# AIRZAI_LID_BD_REVB_Sheet1.net
KiCad netlist of a schematic drawn in Altium Designer
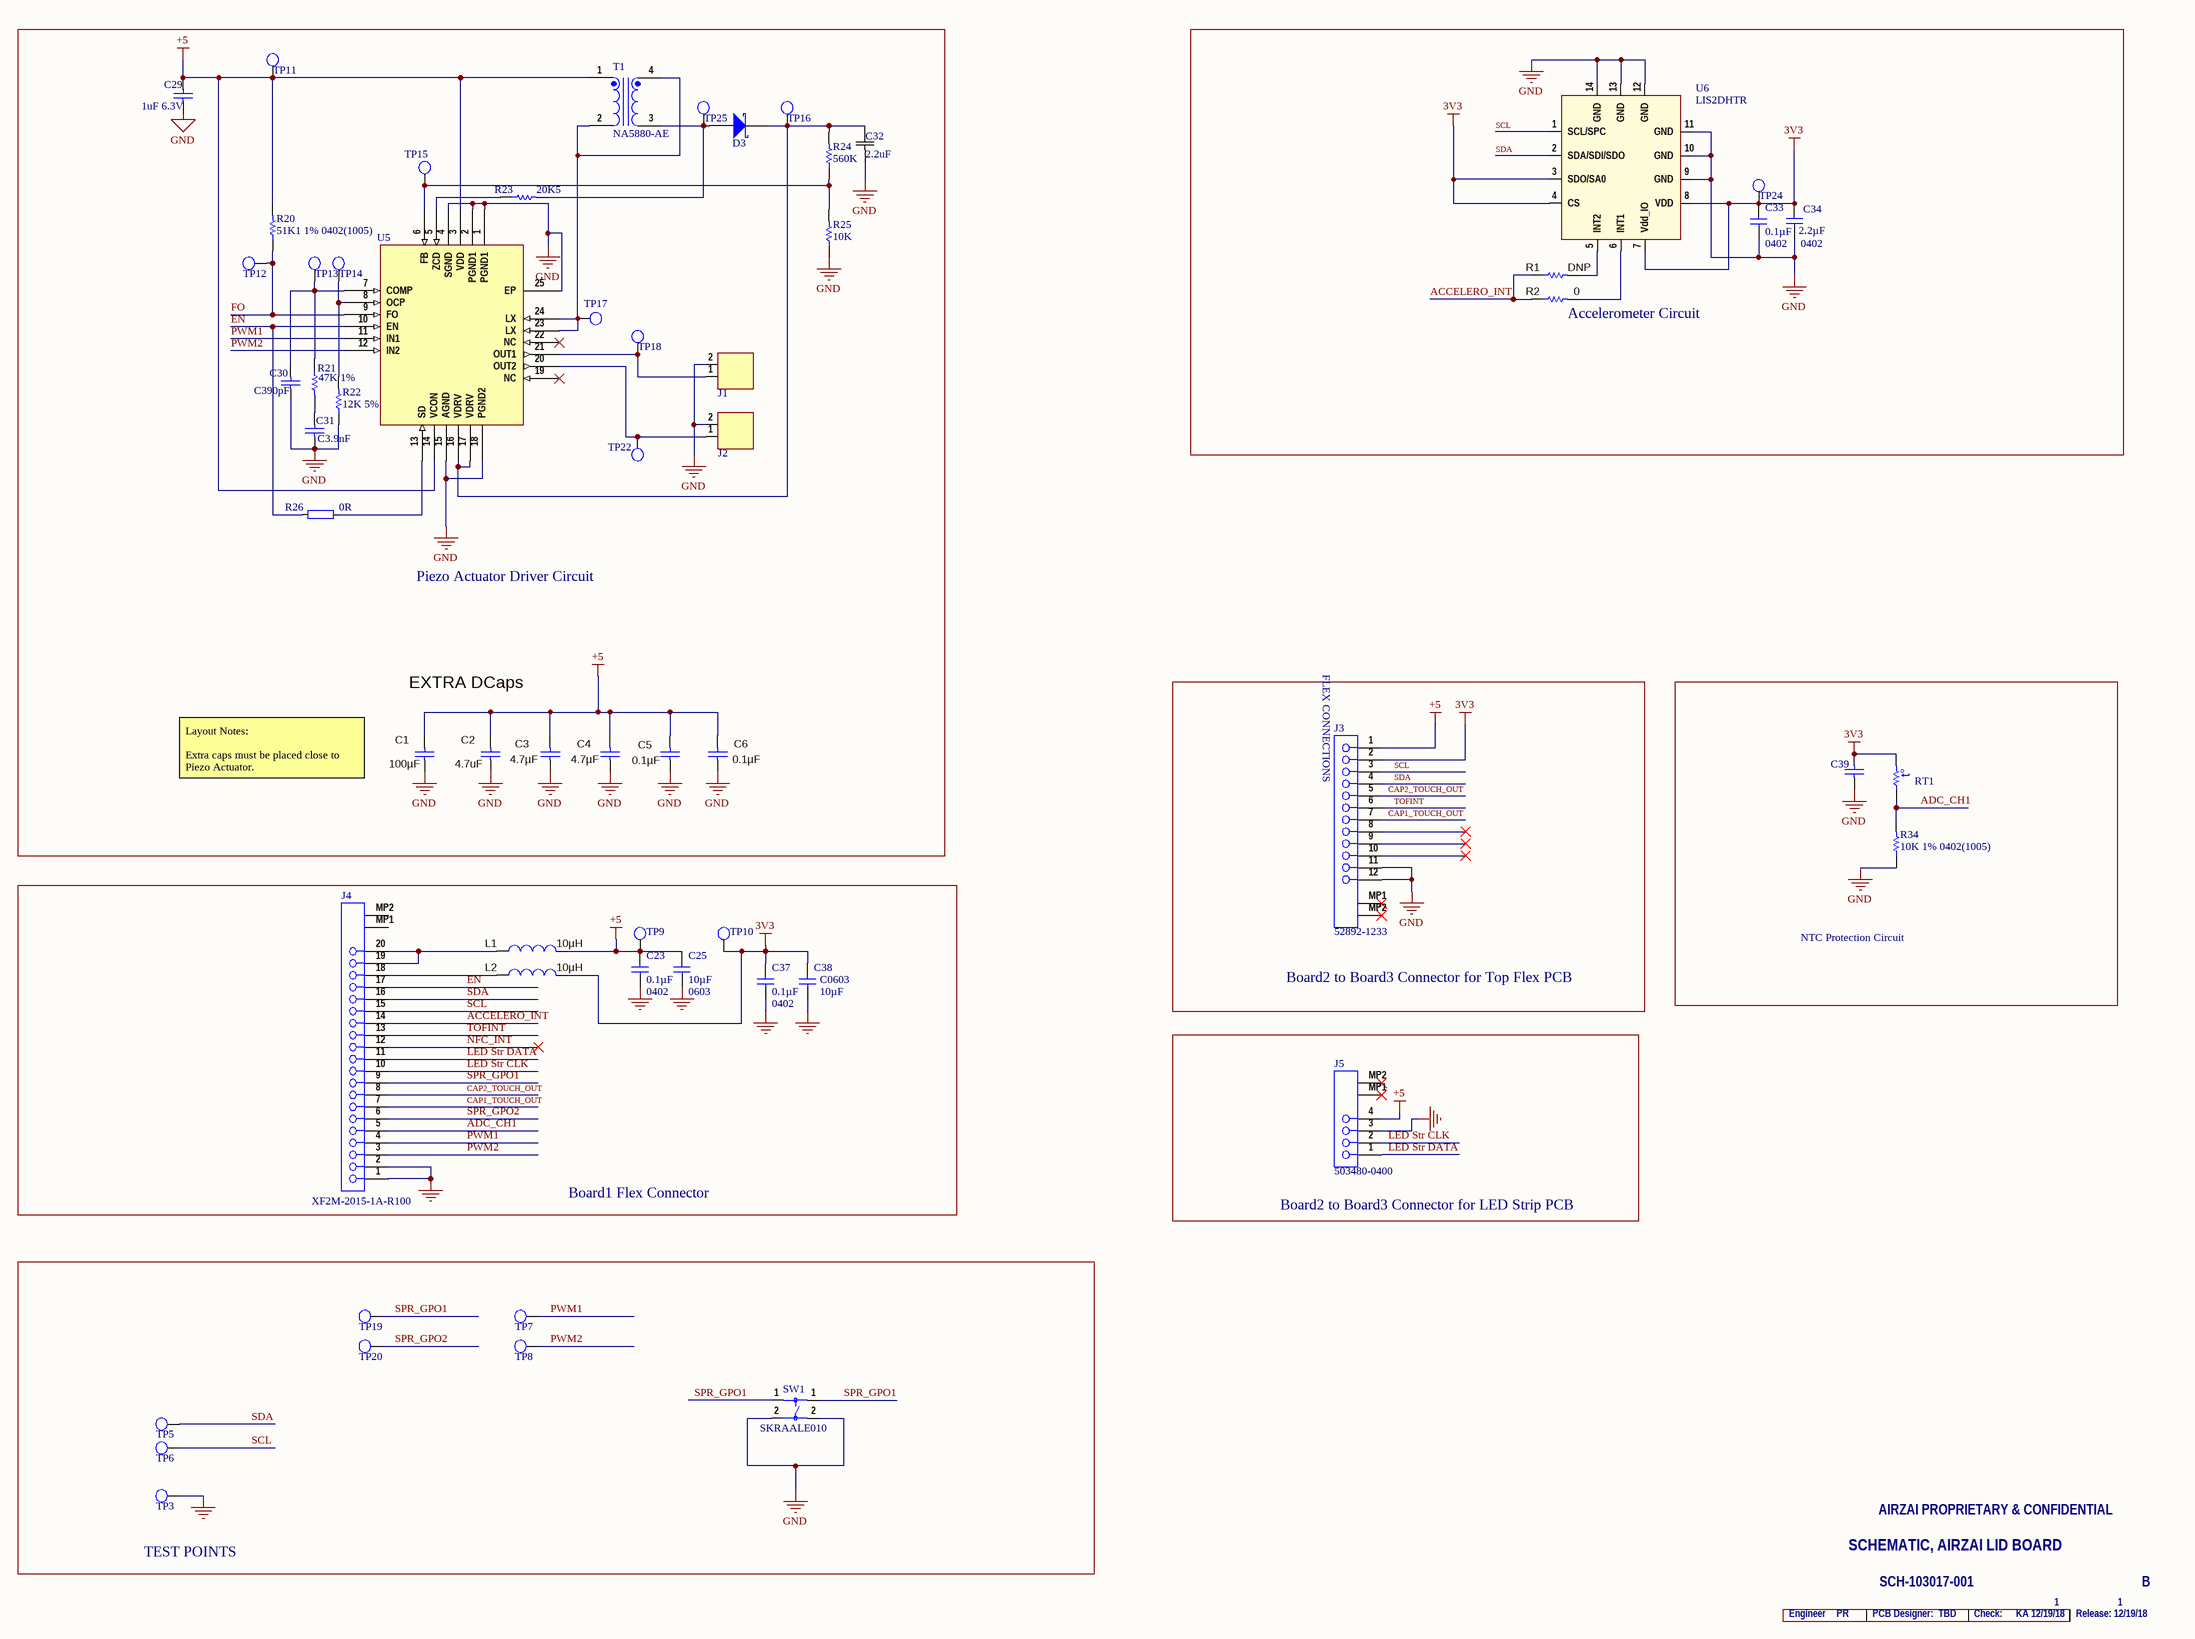
[diagram p0: AIRZAI_LID_BD_REVB Sheet1.SchDoc]

(export (version "E")
  (design (tool "Eeschema 10.0.6"))
  (components
    (comp (ref "C1")
      (value "GRM31CR60J107ME39L")
      (footprint "1206_180")
      (description "CAP, CERM, 100 µF, 6.3 V, +/- 20%, X5R, 1206")
      (fields
        (field (name "VALUEDISPLAYED") "100µF")
        (field (name "MANUFACTURER") "MuRata")
        (field (name "PUBLISHER") "Texas Instruments")
      )
      (libsource (lib "Capacitor_Ceramic") (part "GRM31CR60J107ME39L"))
    )
    (comp (ref "C2")
      (value "4.7uF")
      (footprint "SM0402_BTD.1SM_ACT_H55_CAP_WSS")
      (description "CAP, CERM, 4.7 µF, 6.3 V, +/- 20%, X5R, 0402")
      (fields (field (name "PARTNUMBER") "C1005X5R0J475M050BC") (field (name "MANUFACTURER") "TDK"))
      (libsource (lib "Capacitor_Ceramic") (part "C1005X5R0J475M050BC"))
    )
    (comp (ref "C3")
      (value "C1005X5R0J475M050BC")
      (footprint "SM0402_BTD.1SM_ACT_H55_CAP_WSS")
      (description "CAP, CERM, 4.7 µF, 6.3 V, +/- 20%, X5R, 0402")
      (fields
        (field (name "VALUEDISPLAYED") "4.7µF")
        (field (name "MANUFACTURER") "TDK")
        (field (name "PUBLISHER") "Texas Instruments")
      )
      (libsource (lib "Capacitor_Ceramic") (part "C1005X5R0J475M050BC"))
    )
    (comp (ref "C4")
      (value "C1005X5R0J475M050BC")
      (footprint "SM0402_BTD.1SM_ACT_H55_CAP_WSS")
      (description "CAP, CERM, 4.7 µF, 6.3 V, +/- 20%, X5R, 0402")
      (fields
        (field (name "VALUEDISPLAYED") "4.7µF")
        (field (name "MANUFACTURER") "TDK")
        (field (name "PUBLISHER") "Texas Instruments")
      )
      (libsource (lib "Capacitor_Ceramic") (part "C1005X5R0J475M050BC"))
    )
    (comp (ref "C5")
      (value "C1005X5R1A104K050BA")
      (footprint "SM0402_BTD.1SM_ACT_H55_CAP_WSS")
      (description "CAP, CERM, 0.1 µF, 10 V, +/- 10%, X5R, 0402")
      (fields
        (field (name "VALUEDISPLAYED") "0.1µF")
        (field (name "MANUFACTURER") "TDK")
        (field (name "PUBLISHER") "Texas Instruments")
      )
      (libsource (lib "Capacitor_Ceramic") (part "C1005X5R1A104K050BA"))
    )
    (comp (ref "C6")
      (value "C1005X5R1A104K050BA")
      (footprint "SM0402_BTD.1SM_ACT_H55_CAP_WSS")
      (description "CAP, CERM, 0.1 µF, 10 V, +/- 10%, X5R, 0402")
      (fields
        (field (name "VALUEDISPLAYED") "0.1µF")
        (field (name "MANUFACTURER") "TDK")
        (field (name "PUBLISHER") "Texas Instruments")
      )
      (libsource (lib "Capacitor_Ceramic") (part "C1005X5R1A104K050BA"))
    )
    (comp (ref "C23")
      (value "0.1µF")
      (footprint "0402")
      (description "Capacitor, X7R, ±10%")
      (fields (field (name "MANUFACTURER") "TDK") (field (name "MANUFACTURER PART NUMBER") "C1005X7R1C104K"))
      (libsource (lib "Nordic Passive DB") (part "CAP"))
    )
    (comp (ref "C25")
      (value "10µF")
      (footprint "0603")
      (description "6.3volts X5R 20%")
      (fields
        (field (name "MANUFACTURER") "MURATA")
        (field (name "MANUFACTURER PART NUMBER") "GRM188R60J106ME47D")
      )
      (libsource (lib "Nordic Passive DB") (part "CAP"))
    )
    (comp (ref "C29")
      (value "1uF 6.3V")
      (footprint "CAPC0402(1005)60_M")
      (description "CAP 1uF 6.3V ±10% 0402 (1005 Metric) Thickness 0.6mm SMD")
      (fields (field (name "TOLERANCE") "Â±10%") (field (name "MANUFACTURER") "MURATA"))
      (libsource (lib "") (part "CAP_1"))
    )
    (comp (ref "C30")
      (value "C390pF")
      (footprint "CAPC0402(1005)60_M")
      (description "CAP 390pF 50V ±20% 0402 (1005 Metric) Thickness 0.6mm SMD")
      (fields (field (name "TOLERANCE") "Â±20%") (field (name "MANUFACTURER") "KEMET"))
      (libsource (lib "AIRZAI_LID_BD_REVA") (part "CAP"))
    )
    (comp (ref "C31")
      (value "C3.9nF")
      (footprint "CAPC0402(1005)60_M")
      (description "CAP 3.9nF 50V ±10% 0402 (1005 Metric) Thickness 0.6mm SMD")
      (fields (field (name "TOLERANCE") "Â±10%") (field (name "MANUFACTURER") "TDK"))
      (libsource (lib "") (part "CAP_1"))
    )
    (comp (ref "C32")
      (value "2.2uF")
      (footprint "C1210_N")
      (description "Imported")
      (fields
        (field (name "MANUFACTURER_PART_NUMBER") "C3225JB2A225K230AB")
        (field (name "MANUFACTURER") "TDK")
      )
      (libsource (lib "C3225JB2A225K230AB") (part "C3225JB2A225K230"))
    )
    (comp (ref "C33")
      (value "0.1µF")
      (footprint "0402")
      (description "Capacitor, X7R, ±10%")
      (fields (field (name "MANUFACTURER") "TDK") (field (name "MANUFACTURER PART NUMBER") "C1005X7R1C104K"))
      (libsource (lib "Nordic Passive DB") (part "CAP"))
    )
    (comp (ref "C34")
      (value "2.2µF")
      (footprint "0402")
      (description "Capacitor, X7R, ±10%")
      (fields (field (name "MANUFACTURER") "TDK") (field (name "MANUFACTURER PART NUMBER") "C1005X5R0J225M"))
      (libsource (lib "Nordic Passive DB") (part "CAP"))
    )
    (comp (ref "C37")
      (value "0.1µF")
      (footprint "0402")
      (description "Capacitor, X7R, ±10%")
      (fields (field (name "MANUFACTURER") "TDK") (field (name "MANUFACTURER PART NUMBER") "C1005X7R1C104K"))
      (libsource (lib "Nordic Passive DB") (part "CAP"))
    )
    (comp (ref "C38")
      (value "10µF")
      (footprint "C0603")
      (description "Capacitor, X7R, ±10%")
      (fields
        (field (name "MANUFACTURER") "MURATA")
        (field (name "MANUFACTURER PART NUMBER") "GRM188R60J106ME47D")
      )
      (libsource (lib "Nordic Passive DB") (part "CAP"))
    )
    (comp (ref "C39")
      (value "CAP 100nF 10V 0402(1005)")
      (footprint "CAPC0402(1005)60_M")
      (description "CAP 100nF 10V ±10% 0402 (1005 Metric) Thickness 0.6mm SMD")
      (fields (field (name "TOLERANCE") "Â±10%") (field (name "MANUFACTURER") "Yageo"))
      (libsource (lib "") (part "CAP_1"))
    )
    (comp (ref "D3")
      (value "STPS2H100A")
      (footprint "STM-SMA-2_V")
      (description "Power Schottky Rectifier, 2 A, 100 V, 2-Pin SMD (SMA), RoHS, Tape and Reel")
      (fields (field (name "MANUFACTURER") "STMicroelectronics"))
      (libsource (lib "AIRZAI_LID_BD_REVA") (part "DSKY-AK-2"))
    )
    (comp (ref "J1")
      (value "~")
      (footprint "CON_78171_0002")
      (fields (field (name "MANUFACTURER PART NUMBER") "781710002") (field (name "MANUFACTURER") "MOLEX"))
      (libsource (lib "DFM_JBKEGSVS_Library") (part "CONN_BM02B_SURS_TF"))
    )
    (comp (ref "J2")
      (value "~")
      (footprint "CON_78171_0002")
      (fields (field (name "MANUFACTURER PART NUMBER") "781710002") (field (name "MANUFACTURER") "MOLEX"))
      (libsource (lib "DFM_JBKEGSVS_Library") (part "CONN_BM02B_SURS_TF"))
    )
    (comp (ref "J3")
      (value "52892-1233")
      (footprint "MOLX-52892-1233")
      (fields (field (name "MANUFACTURER") "MOLEX") (field (name "MANUFACTURER PART NUMBER") "0528921233"))
      (libsource (lib "AIRZAI_LID_BD_REVA") (part "MOLX-52892-1233"))
    )
    (comp (ref "J4")
      (value "XF2M-2015-1A-R100")
      (footprint "Omron_XF2M-2015-1A_0")
      (fields (field (name "MANUFACTURER") "OMRON ELECTRONIC COMPONENTS"))
      (libsource (lib "AIRZAI_LID_BD_REVA") (part "XF2M-2015-1A-R100"))
    )
    (comp (ref "J5")
      (value "503480-0400")
      (footprint "MOLX-503480-0400")
      (fields (field (name "MANUFACTURER") "Molex"))
      (libsource (lib "AIRZAI_LID_BD_REVA") (part "503480-0400"))
    )
    (comp (ref "L1")
      (value "CB2012T100KR")
      (footprint "0805")
      (description "Inductor, 10 µH, 0.5A, 0.65 ohm, SMD")
      (fields
        (field (name "MANUFACTURER") "Taiyo Yuden")
        (field (name "TOLERANCE") "10%")
        (field (name "VALUEDISPLAYED") "10µH")
      )
      (libsource (lib "AIRZAI_LED_SENSE_FLEX_REVA") (part "CB2012T100KR"))
    )
    (comp (ref "L2")
      (value "CB2012T100KR")
      (footprint "0805")
      (description "Inductor, 10 µH, 0.5A, 0.65 ohm, SMD")
      (fields
        (field (name "MANUFACTURER") "Taiyo Yuden")
        (field (name "TOLERANCE") "10%")
        (field (name "VALUEDISPLAYED") "10µH")
      )
      (libsource (lib "AIRZAI_LED_SENSE_FLEX_REVA") (part "CB2012T100KR"))
    )
    (comp (ref "R1")
      (value "DNP")
      (footprint "0402")
      (description "RES, DNP, 0402")
      (libsource (lib "Resistor_0402") (part "ERJ-2GE0R00X"))
    )
    (comp (ref "R2")
      (value "ERJ-2GE0R00X")
      (footprint "0402")
      (description "RES, 0, 5%, 0.063 W, 0402")
      (fields
        (field (name "VALUEDISPLAYED") "0")
        (field (name "MANUFACTURER") "Panasonic")
        (field (name "PUBLISHER") "Texas Instruments")
      )
      (libsource (lib "Resistor_0402") (part "ERJ-2GE0R00X"))
    )
    (comp (ref "R20")
      (value "51K1 1% 0402(1005)")
      (footprint "0402")
      (description "51K1 0.063W 1% 0402 (1005 Metric)  SMD")
      (fields (field (name "POWER") "0.063 W") (field (name "TOLERANCE") "1 %"))
      (libsource (lib "AIRZAI_LID_BD_REVA") (part "RES"))
    )
    (comp (ref "R21")
      (value "47K 1%")
      (footprint "0402")
      (description "47K 0.063W 1% 0402 (1005 Metric)  SMD")
      (fields (field (name "POWER") "0.063 W") (field (name "TOLERANCE") "1 %"))
      (libsource (lib "") (part "RES_2"))
    )
    (comp (ref "R22")
      (value "12K 5%")
      (footprint "0402")
      (description "12K 0.063W 5% 0402 (1005 Metric)  SMD")
      (fields (field (name "TOLERANCE") "5 %") (field (name "POWER") "0.063 W"))
      (libsource (lib "AIRZAI_LID_BD_REVA") (part "RES"))
    )
    (comp (ref "R23")
      (value "20K5")
      (footprint "0402")
      (description "20K5 0.063W 1% 0402 (1005 Metric)  SMD")
      (fields (field (name "POWER") "0.063 W") (field (name "TOLERANCE") "1 %"))
      (libsource (lib "") (part "RES_1"))
    )
    (comp (ref "R24")
      (value "560K")
      (footprint "0402")
      (description "560K 0.063W 1% 0402 (1005 Metric)  SMD")
      (fields (field (name "POWER") "0.063 W") (field (name "TOLERANCE") "1 %"))
      (libsource (lib "AIRZAI_LID_BD_REVA") (part "RES"))
    )
    (comp (ref "R25")
      (value "10K")
      (footprint "0402")
      (description "10K 0.063W 5% 0402 (1005 Metric)  SMD")
      (fields (field (name "TOLERANCE") "5 %") (field (name "POWER") "0.063 W"))
      (libsource (lib "AIRZAI_LID_BD_REVA") (part "RES"))
    )
    (comp (ref "R26")
      (value "0R")
      (footprint "0402")
      (description "Resistor, ±1%, 0.063W")
      (fields
        (field (name "MANUFACTURER") "Panasonic")
        (field (name "MANUFACTURER PART NUMBER") "ERJ-2GE0R00X")
      )
      (libsource (lib "Nordic Passive DB") (part "RES_1"))
    )
    (comp (ref "R34")
      (value "10K 1% 0402(1005)")
      (footprint "0402")
      (description "10K 0.063W 1% 0402 (1005 Metric)  SMD")
      (fields (field (name "TOLERANCE") "1 %") (field (name "POWER") "0.063 W"))
      (libsource (lib "AIRZAI_LID_BD_REVA") (part "RES"))
    )
    (comp (ref "RT1")
      (value "NCP18XH103F03RB")
      (footprint "MURA-NCP18XH103F03RB-2_V")
      (description "NTC Thermistor, 10 KOhm, +/- 1%, 0.1 W, -40 to 125 degC, 0603 (1608 Metric), RoHS, Tape and Reel")
      (fields (field (name "MANUFACTURER") "Murata") (field (name "TOLERANCE") "1 %"))
      (libsource (lib "AIRZAI_LID_BD_REVA") (part "MURA-NCP18XH103F03RB-2"))
    )
    (comp (ref "SW1")
      (value "SKRAALE010")
      (footprint "SW_ALPS_SKRAALE010")
      (fields (field (name "MANUFACTURER") "ALPS") (field (name "MANUFACTURER PART NUMBER") "SKRAAKE010"))
      (libsource (lib "DFM_JBKEGSVS_Library") (part "SW_SKRAALE010"))
    )
    (comp (ref "T1")
      (value "NA5880-AE")
      (footprint "Coilcraft_NA5880-AE_MFG")
      (fields (field (name "MANUFACTURER") "CoilCraft") (field (name "TOLERANCE") "20%"))
      (libsource (lib "AIRZAI_LID_BD_REVA") (part "TRANS-DOT-1-1-4"))
    )
    (comp (ref "TP3")
      (value "TESTPOINT")
      (footprint "TP_0.9MM")
      (libsource (lib "DFM_JBKEGSVS_Library") (part "TESTPOINT"))
    )
    (comp (ref "TP5")
      (value "TESTPOINT")
      (footprint "TP_0.9MM")
      (libsource (lib "DFM_JBKEGSVS_Library") (part "TESTPOINT"))
    )
    (comp (ref "TP6")
      (value "TESTPOINT")
      (footprint "TP_0.9MM")
      (libsource (lib "DFM_JBKEGSVS_Library") (part "TESTPOINT"))
    )
    (comp (ref "TP7")
      (value "TESTPOINT")
      (footprint "TP_0.9MM")
      (libsource (lib "DFM_JBKEGSVS_Library") (part "TESTPOINT"))
    )
    (comp (ref "TP8")
      (value "TESTPOINT")
      (footprint "TP_0.9MM")
      (libsource (lib "DFM_JBKEGSVS_Library") (part "TESTPOINT"))
    )
    (comp (ref "TP9")
      (value "TESTPOINT")
      (footprint "TP_0.9MM")
      (libsource (lib "DFM_JBKEGSVS_Library") (part "TESTPOINT"))
    )
    (comp (ref "TP10")
      (value "TESTPOINT")
      (footprint "TP_0.9MM")
      (libsource (lib "DFM_JBKEGSVS_Library") (part "TESTPOINT"))
    )
    (comp (ref "TP11")
      (value "TESTPOINT")
      (footprint "TP_0.9MM")
      (libsource (lib "AIRZAI_LID_BD_REVA") (part "TESTPOINT"))
    )
    (comp (ref "TP12")
      (value "TESTPOINT")
      (footprint "TP_0.9MM")
      (libsource (lib "AIRZAI_LID_BD_REVA") (part "TESTPOINT"))
    )
    (comp (ref "TP13")
      (value "TESTPOINT")
      (footprint "TP_0.9MM")
      (libsource (lib "AIRZAI_LID_BD_REVA") (part "TESTPOINT"))
    )
    (comp (ref "TP14")
      (value "TESTPOINT")
      (footprint "TP_0.9MM")
      (libsource (lib "AIRZAI_LID_BD_REVA") (part "TESTPOINT"))
    )
    (comp (ref "TP15")
      (value "TESTPOINT")
      (footprint "TP_0.9MM")
      (libsource (lib "AIRZAI_LID_BD_REVA") (part "TESTPOINT"))
    )
    (comp (ref "TP16")
      (value "TESTPOINT")
      (footprint "TP_0.9MM")
      (libsource (lib "AIRZAI_LID_BD_REVA") (part "TESTPOINT"))
    )
    (comp (ref "TP17")
      (value "TESTPOINT")
      (footprint "TP_0.9MM")
      (libsource (lib "AIRZAI_LID_BD_REVA") (part "TESTPOINT"))
    )
    (comp (ref "TP18")
      (value "TESTPOINT")
      (footprint "TP_0.9MM")
      (libsource (lib "AIRZAI_LID_BD_REVA") (part "TESTPOINT"))
    )
    (comp (ref "TP19")
      (value "TESTPOINT")
      (footprint "TP_0.9MM")
      (libsource (lib "DFM_JBKEGSVS_Library") (part "TESTPOINT"))
    )
    (comp (ref "TP20")
      (value "TESTPOINT")
      (footprint "TP_0.9MM")
      (libsource (lib "DFM_JBKEGSVS_Library") (part "TESTPOINT"))
    )
    (comp (ref "TP22")
      (value "TESTPOINT")
      (footprint "TP_0.9MM")
      (libsource (lib "AIRZAI_LID_BD_REVA") (part "TESTPOINT"))
    )
    (comp (ref "TP24")
      (value "TESTPOINT")
      (footprint "TP_0.9MM")
      (libsource (lib "AIRZAI_LID_BD_REVA") (part "TESTPOINT"))
    )
    (comp (ref "TP25")
      (value "TESTPOINT")
      (footprint "TP_0.9MM")
      (libsource (lib "AIRZAI_LID_BD_REVA") (part "TESTPOINT"))
    )
    (comp (ref "U5")
      (value "FAN8841MPXCT-ND")
      (footprint "WFQFN-24-FAN8841MPX")
      (description "IC PIEZO ACTUATOR DVR 24MLP")
      (fields
        (field (name "MANUFACTURER") "ON Semiconductor")
        (field (name "MANUFACTURER PART NUMBER") "FAN8841MPX")
      )
      (libsource (lib "AIRZAI_LID_BD_REVA") (part "FAN8841MPXCT-ND"))
    )
    (comp (ref "U6")
      (value "LIS2DHTR")
      (footprint "STM-LGA-14_L")
      (fields (field (name "MANUFACTURER") "ST"))
      (libsource (lib "AIRZAI_LID_BD_REVA") (part "LIS2DH"))
    )
  )
  (nets
    (net (code "1") (name "+5") (class "Default")
      (node (ref "C1") (pin "1") (pinfunction "1_1") (pintype "passive"))
      (node (ref "C2") (pin "1") (pinfunction "1_1") (pintype "passive"))
      (node (ref "C23") (pin "1") (pinfunction "1_1") (pintype "passive"))
      (node (ref "C25") (pin "1") (pinfunction "1_1") (pintype "passive"))
      (node (ref "C29") (pin "2") (pinfunction "2_2") (pintype "passive"))
      (node (ref "C3") (pin "1") (pinfunction "1_1") (pintype "passive"))
      (node (ref "C4") (pin "1") (pinfunction "1_1") (pintype "passive"))
      (node (ref "C5") (pin "1") (pinfunction "1_1") (pintype "passive"))
      (node (ref "C6") (pin "1") (pinfunction "1_1") (pintype "passive"))
      (node (ref "J3") (pin "1") (pinfunction "1_1") (pintype "passive"))
      (node (ref "J5") (pin "4") (pinfunction "4_4") (pintype "passive"))
      (node (ref "L1") (pin "2") (pinfunction "2_2") (pintype "passive"))
      (node (ref "R20") (pin "2") (pinfunction "2_2") (pintype "passive"))
      (node (ref "T1") (pin "1") (pinfunction "1_1") (pintype "passive"))
      (node (ref "TP11") (pin "1") (pinfunction "1_1") (pintype "passive"))
      (node (ref "TP9") (pin "1") (pinfunction "1_1") (pintype "passive"))
      (node (ref "U5") (pin "14") (pinfunction "VCON_14") (pintype "power_in"))
      (node (ref "U5") (pin "3") (pinfunction "VDD_3") (pintype "power_in"))
    )
    (net (code "2") (name "/ACCELERO_INT") (class "Default")
      (node (ref "J4") (pin "14") (pinfunction "14_14") (pintype "passive"))
      (node (ref "R1") (pin "1") (pinfunction "1_1") (pintype "passive"))
      (node (ref "R2") (pin "1") (pinfunction "1_1") (pintype "passive"))
    )
    (net (code "3") (name "/ADC_CH1") (class "Default")
      (node (ref "J4") (pin "5") (pinfunction "5_5") (pintype "passive"))
      (node (ref "R34") (pin "2") (pinfunction "2_2") (pintype "passive"))
      (node (ref "RT1") (pin "1") (pinfunction "1_1") (pintype "passive"))
    )
    (net (code "4") (name "/CAP1_TOUCH_OUT") (class "Default")
      (node (ref "J3") (pin "7") (pinfunction "7_7") (pintype "passive"))
      (node (ref "J4") (pin "7") (pinfunction "7_7") (pintype "passive"))
    )
    (net (code "5") (name "/CAP2_TOUCH_OUT") (class "Default")
      (node (ref "J3") (pin "5") (pinfunction "5_5") (pintype "passive"))
      (node (ref "J4") (pin "8") (pinfunction "8_8") (pintype "passive"))
    )
    (net (code "6") (name "/EN") (class "Default")
      (node (ref "J4") (pin "17") (pinfunction "17_17") (pintype "passive"))
      (node (ref "R26") (pin "2") (pinfunction "2_2") (pintype "passive"))
      (node (ref "U5") (pin "10") (pinfunction "EN_10") (pintype "input"))
    )
    (net (code "7") (name "/FO") (class "Default")
      (node (ref "R20") (pin "1") (pinfunction "1_1") (pintype "passive"))
      (node (ref "TP12") (pin "1") (pinfunction "1_1") (pintype "passive"))
      (node (ref "U5") (pin "9") (pinfunction "FO_9") (pintype "input"))
    )
    (net (code "8") (name "/LED Str CLK") (class "Default")
      (node (ref "J4") (pin "10") (pinfunction "10_10") (pintype "passive"))
      (node (ref "J5") (pin "2") (pinfunction "2_2") (pintype "passive"))
    )
    (net (code "9") (name "/LED Str DATA") (class "Default")
      (node (ref "J4") (pin "11") (pinfunction "11_11") (pintype "passive"))
      (node (ref "J5") (pin "1") (pinfunction "1_1") (pintype "passive"))
    )
    (net (code "10") (name "/NFC_INT") (class "Default")
      (node (ref "J4") (pin "12") (pinfunction "12_12") (pintype "passive+no_connect"))
    )
    (net (code "11") (name "/PWM1") (class "Default")
      (node (ref "J4") (pin "4") (pinfunction "4_4") (pintype "passive"))
      (node (ref "TP7") (pin "1") (pinfunction "1_1") (pintype "passive"))
      (node (ref "U5") (pin "11") (pinfunction "IN1_11") (pintype "input"))
    )
    (net (code "12") (name "/PWM2") (class "Default")
      (node (ref "J4") (pin "3") (pinfunction "3_3") (pintype "passive"))
      (node (ref "TP8") (pin "1") (pinfunction "1_1") (pintype "passive"))
      (node (ref "U5") (pin "12") (pinfunction "IN2_12") (pintype "input"))
    )
    (net (code "13") (name "/SCL") (class "Default")
      (node (ref "J3") (pin "3") (pinfunction "3_3") (pintype "passive"))
      (node (ref "J4") (pin "15") (pinfunction "15_15") (pintype "passive"))
      (node (ref "TP6") (pin "1") (pinfunction "1_1") (pintype "passive"))
      (node (ref "U6") (pin "1") (pinfunction "SCL/SPC_1") (pintype "passive"))
    )
    (net (code "14") (name "/SDA") (class "Default")
      (node (ref "J3") (pin "4") (pinfunction "4_4") (pintype "passive"))
      (node (ref "J4") (pin "16") (pinfunction "16_16") (pintype "passive"))
      (node (ref "TP5") (pin "1") (pinfunction "1_1") (pintype "passive"))
      (node (ref "U6") (pin "2") (pinfunction "SDA/SDI/SDO_2") (pintype "passive"))
    )
    (net (code "15") (name "/SPR_GPO1") (class "Default")
      (node (ref "J4") (pin "9") (pinfunction "9_9") (pintype "passive"))
      (node (ref "SW1") (pin "1") (pinfunction "1_1") (pintype "passive"))
      (node (ref "TP19") (pin "1") (pinfunction "1_1") (pintype "passive"))
    )
    (net (code "16") (name "/SPR_GPO2") (class "Default")
      (node (ref "J4") (pin "6") (pinfunction "6_6") (pintype "passive"))
      (node (ref "TP20") (pin "1") (pinfunction "1_1") (pintype "passive"))
    )
    (net (code "17") (name "/TOFINT") (class "Default")
      (node (ref "J3") (pin "6") (pinfunction "6_6") (pintype "passive"))
      (node (ref "J4") (pin "13") (pinfunction "13_13") (pintype "passive"))
    )
    (net (code "18") (name "3V3") (class "Default")
      (node (ref "C33") (pin "1") (pinfunction "1_1") (pintype "passive"))
      (node (ref "C34") (pin "2") (pinfunction "2_2") (pintype "passive"))
      (node (ref "C37") (pin "1") (pinfunction "1_1") (pintype "passive"))
      (node (ref "C38") (pin "1") (pinfunction "1_1") (pintype "passive"))
      (node (ref "C39") (pin "2") (pinfunction "2_2") (pintype "passive"))
      (node (ref "J3") (pin "2") (pinfunction "2_2") (pintype "passive"))
      (node (ref "L2") (pin "2") (pinfunction "2_2") (pintype "passive"))
      (node (ref "RT1") (pin "2") (pinfunction "2_2") (pintype "passive"))
      (node (ref "TP10") (pin "1") (pinfunction "1_1") (pintype "passive"))
      (node (ref "TP24") (pin "1") (pinfunction "1_1") (pintype "passive"))
      (node (ref "U6") (pin "3") (pinfunction "SDO/SA0_3") (pintype "passive"))
      (node (ref "U6") (pin "4") (pinfunction "CS_4") (pintype "passive"))
      (node (ref "U6") (pin "7") (pinfunction "Vdd_IO_7") (pintype "passive"))
      (node (ref "U6") (pin "8") (pinfunction "VDD_8") (pintype "passive"))
    )
    (net (code "19") (name "GND") (class "Default")
      (node (ref "C1") (pin "2") (pinfunction "2_2") (pintype "passive"))
      (node (ref "C2") (pin "2") (pinfunction "2_2") (pintype "passive"))
      (node (ref "C23") (pin "2") (pinfunction "2_2") (pintype "passive"))
      (node (ref "C25") (pin "2") (pinfunction "2_2") (pintype "passive"))
      (node (ref "C29") (pin "1") (pinfunction "1_1") (pintype "passive"))
      (node (ref "C3") (pin "2") (pinfunction "2_2") (pintype "passive"))
      (node (ref "C30") (pin "2") (pinfunction "2_2") (pintype "passive"))
      (node (ref "C31") (pin "1") (pinfunction "1_1") (pintype "passive"))
      (node (ref "C32") (pin "1") (pinfunction "1_1") (pintype "passive"))
      (node (ref "C33") (pin "2") (pinfunction "2_2") (pintype "passive"))
      (node (ref "C34") (pin "1") (pinfunction "1_1") (pintype "passive"))
      (node (ref "C37") (pin "2") (pinfunction "2_2") (pintype "passive"))
      (node (ref "C38") (pin "2") (pinfunction "2_2") (pintype "passive"))
      (node (ref "C39") (pin "1") (pinfunction "1_1") (pintype "passive"))
      (node (ref "C4") (pin "2") (pinfunction "2_2") (pintype "passive"))
      (node (ref "C5") (pin "2") (pinfunction "2_2") (pintype "passive"))
      (node (ref "C6") (pin "2") (pinfunction "2_2") (pintype "passive"))
      (node (ref "J1") (pin "2") (pinfunction "2_2") (pintype "passive"))
      (node (ref "J2") (pin "2") (pinfunction "2_2") (pintype "passive"))
      (node (ref "J3") (pin "11") (pinfunction "11_11") (pintype "passive"))
      (node (ref "J3") (pin "12") (pinfunction "12_12") (pintype "passive"))
      (node (ref "J4") (pin "1") (pinfunction "1_1") (pintype "passive"))
      (node (ref "J4") (pin "2") (pinfunction "2_2") (pintype "passive"))
      (node (ref "J5") (pin "3") (pinfunction "3_3") (pintype "passive"))
      (node (ref "R22") (pin "1") (pinfunction "1_1") (pintype "passive"))
      (node (ref "R25") (pin "1") (pinfunction "1_1") (pintype "passive"))
      (node (ref "R34") (pin "1") (pinfunction "1_1") (pintype "passive"))
      (node (ref "SW1") (pin "2") (pinfunction "2_2") (pintype "passive"))
      (node (ref "TP3") (pin "1") (pinfunction "1_1") (pintype "passive"))
      (node (ref "U5") (pin "1") (pinfunction "PGND1_1") (pintype "power_in"))
      (node (ref "U5") (pin "15") (pinfunction "AGND_15") (pintype "power_in"))
      (node (ref "U5") (pin "18") (pinfunction "PGND2_18") (pintype "power_in"))
      (node (ref "U5") (pin "2") (pinfunction "PGND1_2") (pintype "power_in"))
      (node (ref "U5") (pin "25") (pinfunction "EP_25") (pintype "passive"))
      (node (ref "U5") (pin "4") (pinfunction "SGND_4") (pintype "power_in"))
      (node (ref "U6") (pin "10") (pinfunction "GND_10") (pintype "passive"))
      (node (ref "U6") (pin "11") (pinfunction "GND_11") (pintype "passive"))
      (node (ref "U6") (pin "12") (pinfunction "GND_12") (pintype "passive"))
      (node (ref "U6") (pin "13") (pinfunction "GND_13") (pintype "passive"))
      (node (ref "U6") (pin "14") (pinfunction "GND_14") (pintype "passive"))
      (node (ref "U6") (pin "9") (pinfunction "GND_9") (pintype "passive"))
    )
    (net (code "20") (name "Net-(C31-Pad2)") (class "Default")
      (node (ref "C31") (pin "2") (pinfunction "2_2") (pintype "passive"))
      (node (ref "R21") (pin "2") (pinfunction "2_2") (pintype "passive"))
    )
    (net (code "21") (name "Net-(D3-A)") (class "Default")
      (node (ref "D3") (pin "1") (pinfunction "A_1") (pintype "passive"))
      (node (ref "R23") (pin "2") (pinfunction "2_2") (pintype "passive"))
      (node (ref "T1") (pin "3") (pinfunction "3_3") (pintype "passive"))
      (node (ref "TP25") (pin "1") (pinfunction "1_1") (pintype "passive"))
    )
    (net (code "22") (name "Net-(D3-K)") (class "Default")
      (node (ref "C32") (pin "2") (pinfunction "2_2") (pintype "passive"))
      (node (ref "D3") (pin "2") (pinfunction "K_2") (pintype "passive"))
      (node (ref "R24") (pin "2") (pinfunction "2_2") (pintype "passive"))
      (node (ref "TP16") (pin "1") (pinfunction "1_1") (pintype "passive"))
      (node (ref "U5") (pin "16") (pinfunction "VDRV_16") (pintype "power_in"))
      (node (ref "U5") (pin "17") (pinfunction "VDRV_17") (pintype "power_in"))
    )
    (net (code "23") (name "Net-(J4-Pad18)") (class "Default")
      (node (ref "J4") (pin "18") (pinfunction "18_18") (pintype "passive"))
      (node (ref "L2") (pin "1") (pinfunction "1_1") (pintype "passive"))
    )
    (net (code "24") (name "Net-(J4-Pad19)") (class "Default")
      (node (ref "J4") (pin "19") (pinfunction "19_19") (pintype "passive"))
      (node (ref "J4") (pin "20") (pinfunction "20_20") (pintype "passive"))
      (node (ref "L1") (pin "1") (pinfunction "1_1") (pintype "passive"))
    )
    (net (code "25") (name "Net-(T1-Pad2)") (class "Default")
      (node (ref "T1") (pin "2") (pinfunction "2_2") (pintype "passive"))
      (node (ref "T1") (pin "4") (pinfunction "4_4") (pintype "passive"))
      (node (ref "TP17") (pin "1") (pinfunction "1_1") (pintype "passive"))
      (node (ref "U5") (pin "23") (pinfunction "LX_23") (pintype "input"))
      (node (ref "U5") (pin "24") (pinfunction "LX_24") (pintype "input"))
    )
    (net (code "26") (name "Net-(U5-COMP)") (class "Default")
      (node (ref "C30") (pin "1") (pinfunction "1_1") (pintype "passive"))
      (node (ref "R21") (pin "1") (pinfunction "1_1") (pintype "passive"))
      (node (ref "TP13") (pin "1") (pinfunction "1_1") (pintype "passive"))
      (node (ref "U5") (pin "7") (pinfunction "COMP_7") (pintype "input"))
    )
    (net (code "27") (name "Net-(U5-FB)") (class "Default")
      (node (ref "R24") (pin "1") (pinfunction "1_1") (pintype "passive"))
      (node (ref "R25") (pin "2") (pinfunction "2_2") (pintype "passive"))
      (node (ref "TP15") (pin "1") (pinfunction "1_1") (pintype "passive"))
      (node (ref "U5") (pin "6") (pinfunction "FB_6") (pintype "input"))
    )
    (net (code "28") (name "Net-(U5-OCP)") (class "Default")
      (node (ref "R22") (pin "2") (pinfunction "2_2") (pintype "passive"))
      (node (ref "TP14") (pin "1") (pinfunction "1_1") (pintype "passive"))
      (node (ref "U5") (pin "8") (pinfunction "OCP_8") (pintype "input"))
    )
    (net (code "29") (name "Net-(U5-OUT1)") (class "Default")
      (node (ref "J1") (pin "1") (pinfunction "1_1") (pintype "passive"))
      (node (ref "TP18") (pin "1") (pinfunction "1_1") (pintype "passive"))
      (node (ref "U5") (pin "21") (pinfunction "OUT1_21") (pintype "output"))
    )
    (net (code "30") (name "Net-(U5-OUT2)") (class "Default")
      (node (ref "J2") (pin "1") (pinfunction "1_1") (pintype "passive"))
      (node (ref "TP22") (pin "1") (pinfunction "1_1") (pintype "passive"))
      (node (ref "U5") (pin "20") (pinfunction "OUT2_20") (pintype "output"))
    )
    (net (code "31") (name "Net-(U5-SD)") (class "Default")
      (node (ref "R26") (pin "1") (pinfunction "1_1") (pintype "passive"))
      (node (ref "U5") (pin "13") (pinfunction "SD_13") (pintype "input"))
    )
    (net (code "32") (name "Net-(U5-ZCD)") (class "Default")
      (node (ref "R23") (pin "1") (pinfunction "1_1") (pintype "passive"))
      (node (ref "U5") (pin "5") (pinfunction "ZCD_5") (pintype "input"))
    )
    (net (code "33") (name "Net-(U6-INT1)") (class "Default")
      (node (ref "R2") (pin "2") (pinfunction "2_2") (pintype "passive"))
      (node (ref "U6") (pin "6") (pinfunction "INT1_6") (pintype "passive"))
    )
    (net (code "34") (name "Net-(U6-INT2)") (class "Default")
      (node (ref "R1") (pin "2") (pinfunction "2_2") (pintype "passive"))
      (node (ref "U6") (pin "5") (pinfunction "INT2_5") (pintype "passive"))
    )
    (net (code "35") (name "unconnected-(J3-Pad8)") (class "Default")
      (node (ref "J3") (pin "8") (pinfunction "8_8") (pintype "passive+no_connect"))
    )
    (net (code "36") (name "unconnected-(J3-Pad9)") (class "Default")
      (node (ref "J3") (pin "9") (pinfunction "9_9") (pintype "passive+no_connect"))
    )
    (net (code "37") (name "unconnected-(J3-Pad10)") (class "Default")
      (node (ref "J3") (pin "10") (pinfunction "10_10") (pintype "passive+no_connect"))
    )
    (net (code "38") (name "unconnected-(J3-PadMP1)") (class "Default")
      (node (ref "J3") (pin "MP1") (pinfunction "MP1_MP1") (pintype "passive+no_connect"))
    )
    (net (code "39") (name "unconnected-(J3-PadMP2)") (class "Default")
      (node (ref "J3") (pin "MP2") (pinfunction "MP2_MP2") (pintype "passive+no_connect"))
    )
    (net (code "40") (name "unconnected-(J4-PadMP1)") (class "Default")
      (node (ref "J4") (pin "MP1") (pinfunction "MP1_MP1") (pintype "passive"))
    )
    (net (code "41") (name "unconnected-(J4-PadMP2)") (class "Default")
      (node (ref "J4") (pin "MP2") (pinfunction "MP2_MP2") (pintype "passive"))
    )
    (net (code "42") (name "unconnected-(J5-PadMP1)") (class "Default")
      (node (ref "J5") (pin "MP1") (pinfunction "MP1_MP1") (pintype "passive+no_connect"))
    )
    (net (code "43") (name "unconnected-(J5-PadMP2)") (class "Default")
      (node (ref "J5") (pin "MP2") (pinfunction "MP2_MP2") (pintype "passive+no_connect"))
    )
    (net (code "44") (name "unconnected-(U5-NC-Pad19)") (class "Default")
      (node (ref "U5") (pin "19") (pinfunction "NC_19") (pintype "input+no_connect"))
    )
    (net (code "45") (name "unconnected-(U5-NC-Pad22)") (class "Default")
      (node (ref "U5") (pin "22") (pinfunction "NC_22") (pintype "input+no_connect"))
    )
  )
)
